# SparkFun_LTE_Stick_LARA_R6.net
KiCad netlist of a schematic drawn in EAGLE
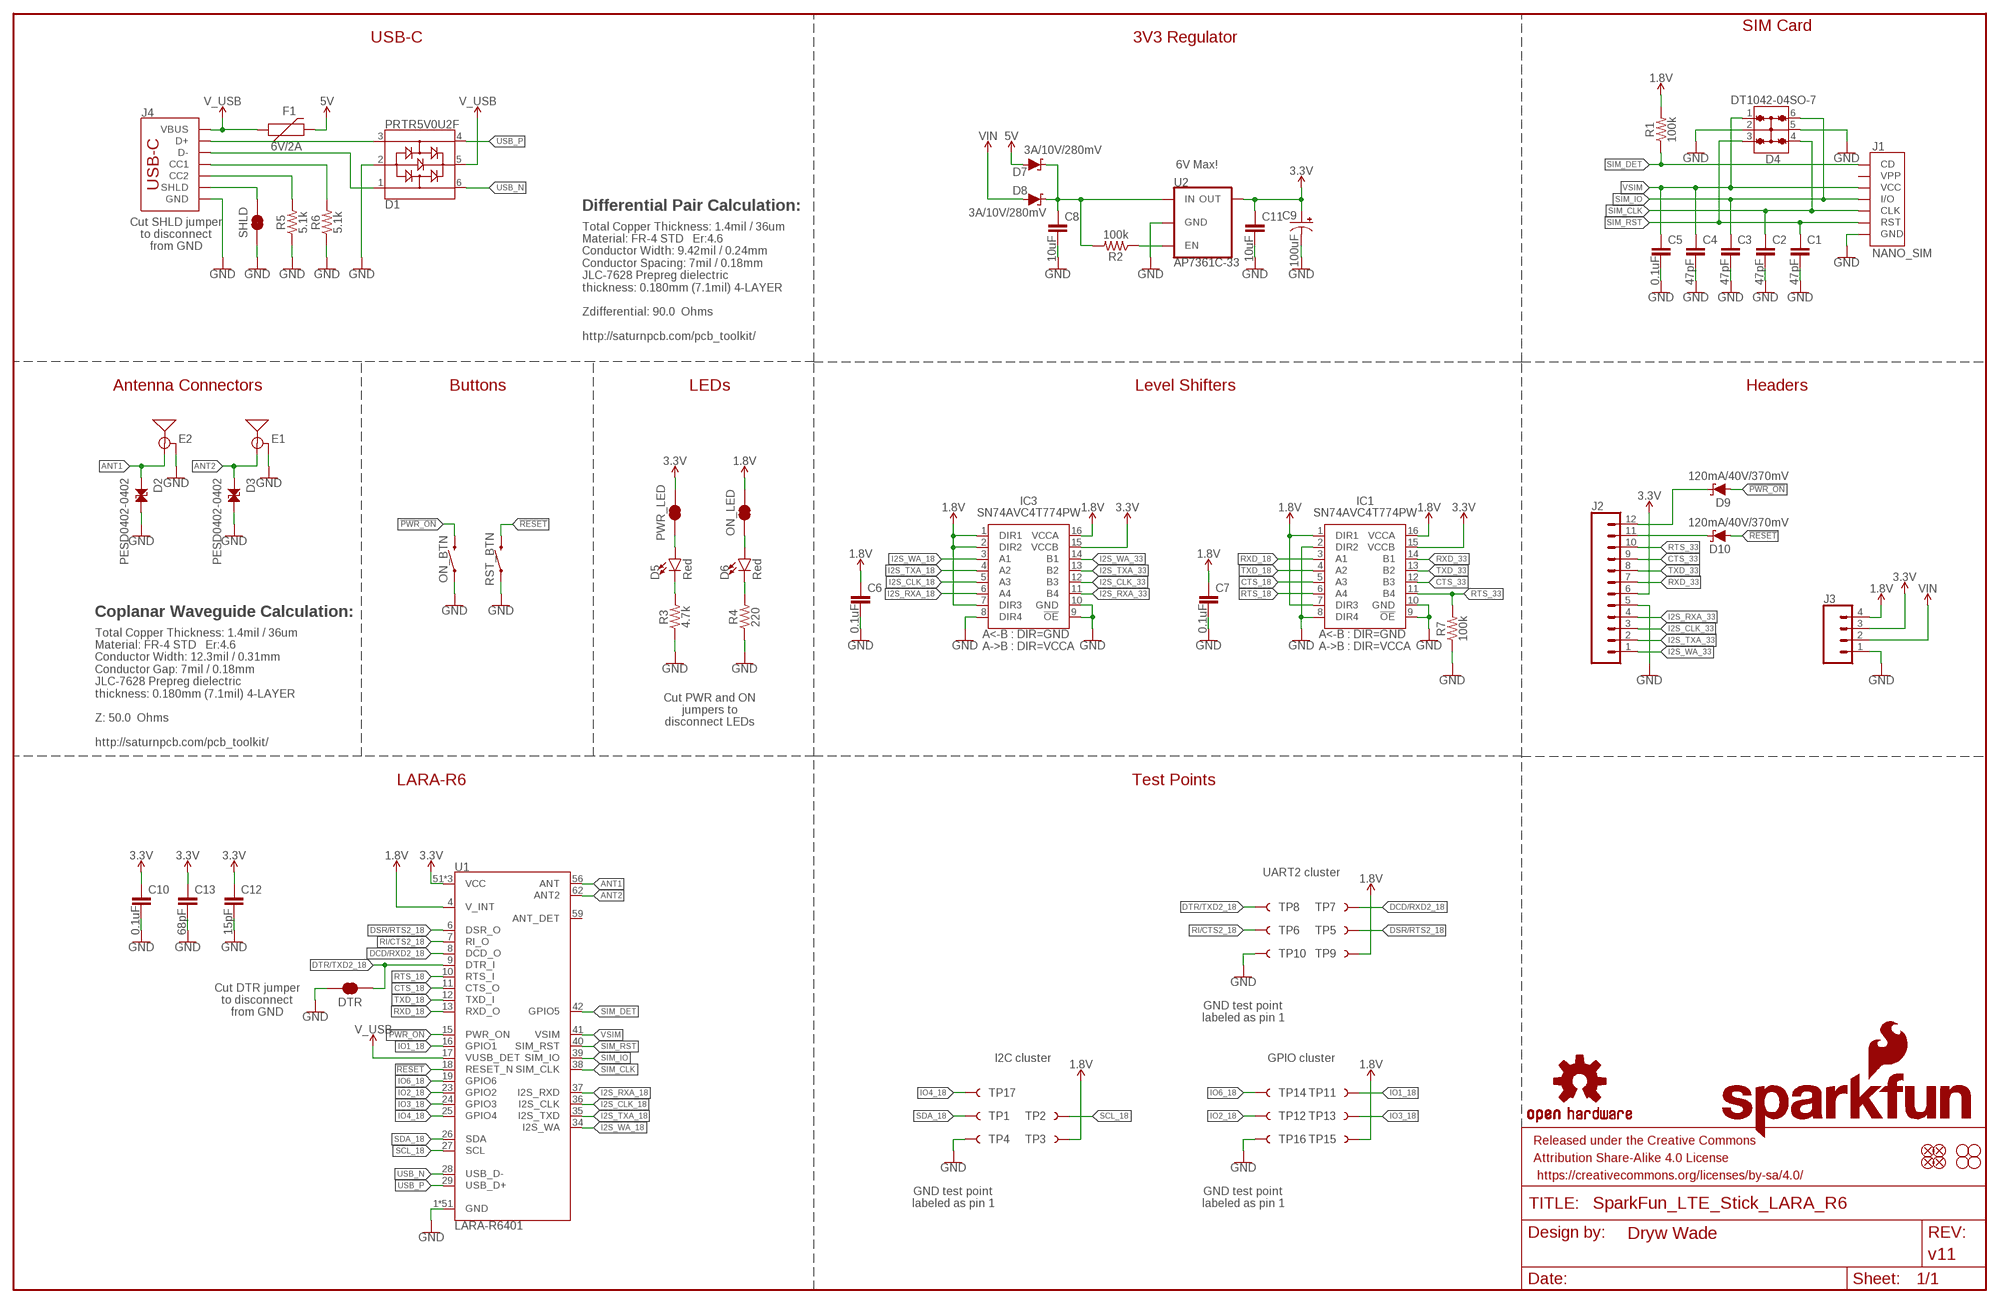
[diagram p0: schematic, sheet 1]

(export (version "E")
  (design (tool "Eeschema 10.0.6"))
  (components
    (comp (ref "C1")
      (value "47pF")
      (footprint "eagle-import:0603")
      (libsource (lib "eagle-import") (part "47PF-0603-50V-5%"))
    )
    (comp (ref "C2")
      (value "47pF")
      (footprint "eagle-import:0603")
      (libsource (lib "eagle-import") (part "47PF-0603-50V-5%"))
    )
    (comp (ref "C3")
      (value "47pF")
      (footprint "eagle-import:0603")
      (libsource (lib "eagle-import") (part "47PF-0603-50V-5%"))
    )
    (comp (ref "C4")
      (value "47pF")
      (footprint "eagle-import:0603")
      (libsource (lib "eagle-import") (part "47PF-0603-50V-5%"))
    )
    (comp (ref "C5")
      (value "0.1uF")
      (footprint "eagle-import:0603")
      (libsource (lib "eagle-import") (part "0.1UF-0603-25V-5%"))
    )
    (comp (ref "C6")
      (value "0.1uF")
      (footprint "eagle-import:0603")
      (libsource (lib "eagle-import") (part "0.1UF-0603-25V-5%"))
    )
    (comp (ref "C7")
      (value "0.1uF")
      (footprint "eagle-import:0603")
      (libsource (lib "eagle-import") (part "0.1UF-0603-25V-5%"))
    )
    (comp (ref "C8")
      (value "10uF")
      (footprint "eagle-import:0805")
      (libsource (lib "eagle-import") (part "10UF-0805-25V-10%"))
    )
    (comp (ref "C9")
      (value "100uF")
      (footprint "eagle-import:PANASONIC_D")
      (libsource (lib "eagle-import") (part "100UF-POLAR-35V-20%(ELEC)"))
    )
    (comp (ref "C10")
      (value "0.1uF")
      (footprint "eagle-import:0603")
      (libsource (lib "eagle-import") (part "0.1UF-0603-25V-5%"))
    )
    (comp (ref "C11")
      (value "10uF")
      (footprint "eagle-import:0805")
      (libsource (lib "eagle-import") (part "10UF-0805-25V-10%"))
    )
    (comp (ref "C12")
      (value "15pF")
      (footprint "eagle-import:0603")
      (libsource (lib "eagle-import") (part "15PF-0603-50V-5%"))
    )
    (comp (ref "C13")
      (value "68pF")
      (footprint "eagle-import:0603")
      (libsource (lib "eagle-import") (part "68PF-0603-50V-5%"))
    )
    (comp (ref "D1")
      (value "PRTR5V0U2F")
      (footprint "eagle-import:SOT886")
      (libsource (lib "eagle-import") (part "PRTR5V0U2F"))
    )
    (comp (ref "D2")
      (value "PESD0402-0402")
      (footprint "eagle-import:0402")
      (fields
        (field (name "DIGIKEY_PART") "PESD0402-140CT-ND")
        (field (name "MOUSE_PART") "650-PESD0402-140")
      )
      (libsource (lib "eagle-import") (part "PESD0402-0402"))
    )
    (comp (ref "D3")
      (value "PESD0402-0402")
      (footprint "eagle-import:0402")
      (fields
        (field (name "DIGIKEY_PART") "PESD0402-140CT-ND")
        (field (name "MOUSE_PART") "650-PESD0402-140")
      )
      (libsource (lib "eagle-import") (part "PESD0402-0402"))
    )
    (comp (ref "D4")
      (value "DT1042-04SO-7")
      (footprint "eagle-import:SOT23-6L")
      (libsource (lib "eagle-import") (part "TVS_DIODE_ARRAY_4_ESDA6V1BC6"))
    )
    (comp (ref "D5")
      (value "Red")
      (footprint "eagle-import:LED-0603")
      (libsource (lib "eagle-import") (part "LED-RED_0603-KB"))
    )
    (comp (ref "D6")
      (value "Red")
      (footprint "eagle-import:LED-0603")
      (libsource (lib "eagle-import") (part "LED-RED_0603-KB"))
    )
    (comp (ref "D7")
      (value "3A/10V/280mV")
      (footprint "eagle-import:SOD-323")
      (libsource (lib "eagle-import") (part "DIODE-SCHOTTKY-BAT60A"))
    )
    (comp (ref "D8")
      (value "3A/10V/280mV")
      (footprint "eagle-import:SOD-323")
      (libsource (lib "eagle-import") (part "DIODE-SCHOTTKY-BAT60A"))
    )
    (comp (ref "D9")
      (value "120mA/40V/370mV")
      (footprint "eagle-import:SOD-523")
      (libsource (lib "eagle-import") (part "DIODE-SCHOTTKY-RB751S40"))
    )
    (comp (ref "D10")
      (value "120mA/40V/370mV")
      (footprint "eagle-import:SOD-523")
      (libsource (lib "eagle-import") (part "DIODE-SCHOTTKY-RB751S40"))
    )
    (comp (ref "DTR")
      (value "JUMPER-SMT_2_NC_TRACE_SILK")
      (footprint "eagle-import:SMT-JUMPER_2_NC_TRACE_SILK")
      (libsource (lib "eagle-import") (part "JUMPER-SMT_2_NC_TRACE_SILK"))
    )
    (comp (ref "E1")
      (value "ANTENNA-SMA-GROUNDEDEDGE_SMA")
      (footprint "eagle-import:SMA-EDGE")
      (fields (field (name "PROD_ID") "CONN-19593"))
      (libsource (lib "eagle-import") (part "ANTENNA-SMA-GROUNDEDEDGE_SMA"))
    )
    (comp (ref "E2")
      (value "ANTENNA-SMA-GROUNDEDEDGE_SMA")
      (footprint "eagle-import:SMA-EDGE")
      (fields (field (name "PROD_ID") "CONN-19593"))
      (libsource (lib "eagle-import") (part "ANTENNA-SMA-GROUNDEDEDGE_SMA"))
    )
    (comp (ref "F1")
      (value "6V/2A")
      (footprint "eagle-import:1210")
      (libsource (lib "eagle-import") (part "PPTC_6V2A"))
    )
    (comp (ref "FD1")
      (value "FIDUCIAL1X2")
      (footprint "eagle-import:FIDUCIAL-1X2")
      (libsource (lib "eagle-import") (part "FIDUCIAL1X2"))
    )
    (comp (ref "FD2")
      (value "FIDUCIAL1X2")
      (footprint "eagle-import:FIDUCIAL-1X2")
      (libsource (lib "eagle-import") (part "FIDUCIAL1X2"))
    )
    (comp (ref "FD3")
      (value "FIDUCIAL1X2")
      (footprint "eagle-import:FIDUCIAL-1X2")
      (libsource (lib "eagle-import") (part "FIDUCIAL1X2"))
    )
    (comp (ref "FD4")
      (value "FIDUCIAL1X2")
      (footprint "eagle-import:FIDUCIAL-1X2")
      (libsource (lib "eagle-import") (part "FIDUCIAL1X2"))
    )
    (comp (ref "FRAME1")
      (value "FRAME-LEDGER")
      (footprint "eagle-import:CREATIVE_COMMONS")
      (fields (field (name "DESIGNER") "Dryw Wade") (field (name "REV") "v11"))
      (libsource (lib "eagle-import") (part "FRAME-LEDGER"))
    )
    (comp (ref "H1")
      (value "STAND-OFF")
      (footprint "eagle-import:STAND-OFF")
      (libsource (lib "eagle-import") (part "STAND-OFF"))
    )
    (comp (ref "H2")
      (value "STAND-OFF")
      (footprint "eagle-import:STAND-OFF")
      (libsource (lib "eagle-import") (part "STAND-OFF"))
    )
    (comp (ref "H3")
      (value "STAND-OFF")
      (footprint "eagle-import:STAND-OFF")
      (libsource (lib "eagle-import") (part "STAND-OFF"))
    )
    (comp (ref "H4")
      (value "STAND-OFF")
      (footprint "eagle-import:STAND-OFF")
      (libsource (lib "eagle-import") (part "STAND-OFF"))
    )
    (comp (ref "IC1")
      (value "SN74AVC4T774PW")
      (footprint "eagle-import:SOP65P640X120-16N")
      (libsource (lib "eagle-import") (part "SN74AVC4T774PW"))
    )
    (comp (ref "IC3")
      (value "SN74AVC4T774PW")
      (footprint "eagle-import:SOP65P640X120-16N")
      (libsource (lib "eagle-import") (part "SN74AVC4T774PW"))
    )
    (comp (ref "J1")
      (value "NANO_SIM")
      (footprint "eagle-import:NANO_SIM_PP")
      (libsource (lib "eagle-import") (part "SIMHOLDER_WITH_CD-PUSHPUSH"))
    )
    (comp (ref "J2")
      (value "CONN_12NO_SILK")
      (footprint "eagle-import:1X12_NO_SILK")
      (libsource (lib "eagle-import") (part "CONN_12NO_SILK"))
    )
    (comp (ref "J3")
      (value "CONN_041X04_NO_SILK_NO_POP")
      (footprint "eagle-import:1X04_NO_SILK")
      (libsource (lib "eagle-import") (part "CONN_041X04_NO_SILK_NO_POP"))
    )
    (comp (ref "J4")
      (value "USB_C_4-LAYER_PADS")
      (footprint "eagle-import:USB-C-16P_4LAYER-PADS")
      (libsource (lib "eagle-import") (part "USB_C_4-LAYER_PADS"))
    )
    (comp (ref "LOGO1")
      (value "SFE_LOGO_NAME_FLAME.1_INCH")
      (footprint "eagle-import:SFE_LOGO_NAME_FLAME_.1")
      (libsource (lib "eagle-import") (part "SFE_LOGO_NAME_FLAME.1_INCH"))
    )
    (comp (ref "LOGO2")
      (value "OSHW-LOGOM")
      (footprint "eagle-import:OSHW-LOGO-M")
      (libsource (lib "eagle-import") (part "OSHW-LOGOM"))
    )
    (comp (ref "ON_BTN")
      (value "MOMENTARY-SWITCH-SPST-SMD-4.6X2.8MM")
      (footprint "eagle-import:TACTILE_SWITCH_SMD_4.6X2.8MM")
      (libsource (lib "eagle-import") (part "MOMENTARY-SWITCH-SPST-SMD-4.6X2.8MM"))
    )
    (comp (ref "ON_LED")
      (value "JUMPER-SMT_2_NC_TRACE_SILK")
      (footprint "eagle-import:SMT-JUMPER_2_NC_TRACE_SILK")
      (libsource (lib "eagle-import") (part "JUMPER-SMT_2_NC_TRACE_SILK"))
    )
    (comp (ref "PWR_LED")
      (value "JUMPER-SMT_2_NC_TRACE_SILK")
      (footprint "eagle-import:SMT-JUMPER_2_NC_TRACE_SILK")
      (libsource (lib "eagle-import") (part "JUMPER-SMT_2_NC_TRACE_SILK"))
    )
    (comp (ref "R1")
      (value "100k")
      (footprint "eagle-import:0603")
      (libsource (lib "eagle-import") (part "100KOHM-0603-1/10W-1%"))
    )
    (comp (ref "R2")
      (value "100k")
      (footprint "eagle-import:0603")
      (libsource (lib "eagle-import") (part "100KOHM-0603-1/10W-1%"))
    )
    (comp (ref "R3")
      (value "4.7k")
      (footprint "eagle-import:0603")
      (libsource (lib "eagle-import") (part "4.7KOHM-0603-1/10W-1%"))
    )
    (comp (ref "R4")
      (value "220")
      (footprint "eagle-import:0603")
      (libsource (lib "eagle-import") (part "220OHM-0603-1/10W-1%"))
    )
    (comp (ref "R5")
      (value "5.1k")
      (footprint "eagle-import:0603")
      (libsource (lib "eagle-import") (part "5.1KOHM5.1KOHM-0603-1/10W-1%"))
    )
    (comp (ref "R6")
      (value "5.1k")
      (footprint "eagle-import:0603")
      (libsource (lib "eagle-import") (part "5.1KOHM5.1KOHM-0603-1/10W-1%"))
    )
    (comp (ref "R7")
      (value "100k")
      (footprint "eagle-import:0603")
      (libsource (lib "eagle-import") (part "100KOHM-0603-1/10W-1%"))
    )
    (comp (ref "RST_BTN")
      (value "MOMENTARY-SWITCH-SPST-SMD-4.6X2.8MM")
      (footprint "eagle-import:TACTILE_SWITCH_SMD_4.6X2.8MM")
      (libsource (lib "eagle-import") (part "MOMENTARY-SWITCH-SPST-SMD-4.6X2.8MM"))
    )
    (comp (ref "SHLD")
      (value "JUMPER-SMT_2_NC_TRACE_SILK")
      (footprint "eagle-import:SMT-JUMPER_2_NC_TRACE_SILK")
      (libsource (lib "eagle-import") (part "JUMPER-SMT_2_NC_TRACE_SILK"))
    )
    (comp (ref "TP1")
      (value "TEST-POINT3X5")
      (footprint "eagle-import:PAD.03X.05")
      (libsource (lib "eagle-import") (part "TEST-POINT3X5"))
    )
    (comp (ref "TP2")
      (value "TEST-POINT3X5")
      (footprint "eagle-import:PAD.03X.05")
      (libsource (lib "eagle-import") (part "TEST-POINT3X5"))
    )
    (comp (ref "TP3")
      (value "TEST-POINT3X5")
      (footprint "eagle-import:PAD.03X.05")
      (libsource (lib "eagle-import") (part "TEST-POINT3X5"))
    )
    (comp (ref "TP4")
      (value "TEST-POINT3X5")
      (footprint "eagle-import:PAD.03X.05")
      (libsource (lib "eagle-import") (part "TEST-POINT3X5"))
    )
    (comp (ref "TP5")
      (value "TEST-POINT3X5")
      (footprint "eagle-import:PAD.03X.05")
      (libsource (lib "eagle-import") (part "TEST-POINT3X5"))
    )
    (comp (ref "TP6")
      (value "TEST-POINT3X5")
      (footprint "eagle-import:PAD.03X.05")
      (libsource (lib "eagle-import") (part "TEST-POINT3X5"))
    )
    (comp (ref "TP7")
      (value "TEST-POINT3X5")
      (footprint "eagle-import:PAD.03X.05")
      (libsource (lib "eagle-import") (part "TEST-POINT3X5"))
    )
    (comp (ref "TP8")
      (value "TEST-POINT3X5")
      (footprint "eagle-import:PAD.03X.05")
      (libsource (lib "eagle-import") (part "TEST-POINT3X5"))
    )
    (comp (ref "TP9")
      (value "TEST-POINT3X5")
      (footprint "eagle-import:PAD.03X.05")
      (libsource (lib "eagle-import") (part "TEST-POINT3X5"))
    )
    (comp (ref "TP10")
      (value "TEST-POINT3X5")
      (footprint "eagle-import:PAD.03X.05")
      (libsource (lib "eagle-import") (part "TEST-POINT3X5"))
    )
    (comp (ref "TP11")
      (value "TEST-POINT3X5")
      (footprint "eagle-import:PAD.03X.05")
      (libsource (lib "eagle-import") (part "TEST-POINT3X5"))
    )
    (comp (ref "TP12")
      (value "TEST-POINT3X5")
      (footprint "eagle-import:PAD.03X.05")
      (libsource (lib "eagle-import") (part "TEST-POINT3X5"))
    )
    (comp (ref "TP13")
      (value "TEST-POINT3X5")
      (footprint "eagle-import:PAD.03X.05")
      (libsource (lib "eagle-import") (part "TEST-POINT3X5"))
    )
    (comp (ref "TP14")
      (value "TEST-POINT3X5")
      (footprint "eagle-import:PAD.03X.05")
      (libsource (lib "eagle-import") (part "TEST-POINT3X5"))
    )
    (comp (ref "TP15")
      (value "TEST-POINT3X5")
      (footprint "eagle-import:PAD.03X.05")
      (libsource (lib "eagle-import") (part "TEST-POINT3X5"))
    )
    (comp (ref "TP16")
      (value "TEST-POINT3X5")
      (footprint "eagle-import:PAD.03X.05")
      (libsource (lib "eagle-import") (part "TEST-POINT3X5"))
    )
    (comp (ref "TP17")
      (value "TEST-POINT3X5")
      (footprint "eagle-import:PAD.03X.05")
      (libsource (lib "eagle-import") (part "TEST-POINT3X5"))
    )
    (comp (ref "U1")
      (value "LARA-R6401")
      (footprint "eagle-import:LARA-LGA")
      (libsource (lib "eagle-import") (part "LARA-R6_R6401_USA"))
    )
    (comp (ref "U2")
      (value "AP7361C-33")
      (footprint "eagle-import:UDFN-8")
      (libsource (lib "eagle-import") (part "AP7361C-33FGEUDFN-8"))
    )
  )
  (nets
    (net (code "1") (name "/~{PWR_ON}") (class "Default")
      (node (ref "D9") (pin "A") (pinfunction "A_A") (pintype "passive"))
      (node (ref "ON_BTN") (pin "3") (pinfunction "2_3") (pintype "passive"))
      (node (ref "ON_BTN") (pin "4") (pinfunction "2_4") (pintype "passive"))
      (node (ref "U1") (pin "15") (pinfunction "PWR_ON_15") (pintype "input"))
    )
    (net (code "2") (name "/~{RESET}") (class "Default")
      (node (ref "D10") (pin "A") (pinfunction "A_A") (pintype "passive"))
      (node (ref "RST_BTN") (pin "3") (pinfunction "2_3") (pintype "passive"))
      (node (ref "RST_BTN") (pin "4") (pinfunction "2_4") (pintype "passive"))
      (node (ref "U1") (pin "18") (pinfunction "RESET_N_18") (pintype "input"))
    )
    (net (code "3") (name "1.8V") (class "Default")
      (node (ref "C6") (pin "1") (pinfunction "1_1") (pintype "passive"))
      (node (ref "C7") (pin "1") (pinfunction "1_1") (pintype "passive"))
      (node (ref "IC1") (pin "1") (pinfunction "DIR1_1") (pintype "input"))
      (node (ref "IC1") (pin "16") (pinfunction "VCCA_16") (pintype "power_in"))
      (node (ref "IC1") (pin "7") (pinfunction "DIR3_7") (pintype "input"))
      (node (ref "IC3") (pin "1") (pinfunction "DIR1_1") (pintype "input"))
      (node (ref "IC3") (pin "16") (pinfunction "VCCA_16") (pintype "power_in"))
      (node (ref "IC3") (pin "2") (pinfunction "DIR2_2") (pintype "input"))
      (node (ref "IC3") (pin "7") (pinfunction "DIR3_7") (pintype "input"))
      (node (ref "J3") (pin "4") (pinfunction "4_4") (pintype "passive"))
      (node (ref "ON_LED") (pin "2") (pinfunction "2_2") (pintype "passive"))
      (node (ref "R1") (pin "2") (pinfunction "2_2") (pintype "passive"))
      (node (ref "TP15") (pin "1") (pinfunction "1_1") (pintype "bidirectional"))
      (node (ref "TP3") (pin "1") (pinfunction "1_1") (pintype "bidirectional"))
      (node (ref "TP9") (pin "1") (pinfunction "1_1") (pintype "bidirectional"))
      (node (ref "U1") (pin "4") (pinfunction "V_INT_4") (pintype "output"))
    )
    (net (code "4") (name "3.3V") (class "Default")
      (node (ref "C10") (pin "1") (pinfunction "1_1") (pintype "passive"))
      (node (ref "C11") (pin "1") (pinfunction "1_1") (pintype "passive"))
      (node (ref "C12") (pin "1") (pinfunction "1_1") (pintype "passive"))
      (node (ref "C13") (pin "1") (pinfunction "1_1") (pintype "passive"))
      (node (ref "C9") (pin "+") (pinfunction "+_+") (pintype "passive"))
      (node (ref "IC1") (pin "15") (pinfunction "VCCB_15") (pintype "power_in"))
      (node (ref "IC3") (pin "15") (pinfunction "VCCB_15") (pintype "power_in"))
      (node (ref "J2") (pin "6") (pinfunction "6_6") (pintype "passive"))
      (node (ref "J3") (pin "3") (pinfunction "3_3") (pintype "passive"))
      (node (ref "PWR_LED") (pin "2") (pinfunction "2_2") (pintype "passive"))
      (node (ref "U1") (pin "51") (pinfunction "VCC_51") (pintype "power_in"))
      (node (ref "U1") (pin "52") (pinfunction "VCC_52") (pintype "power_in"))
      (node (ref "U1") (pin "53") (pinfunction "VCC_53") (pintype "power_in"))
      (node (ref "U2") (pin "1") (pinfunction "OUT_1") (pintype "output"))
    )
    (net (code "5") (name "5V") (class "Default")
      (node (ref "D7") (pin "A") (pinfunction "A_A") (pintype "passive"))
      (node (ref "F1") (pin "2") (pinfunction "2_2") (pintype "bidirectional"))
    )
    (net (code "6") (name "ANT1") (class "Default")
      (node (ref "D2") (pin "1") (pinfunction "1_1") (pintype "bidirectional"))
      (node (ref "E2") (pin "SIG") (pinfunction "SIGNAL_SIG") (pintype "bidirectional"))
      (node (ref "U1") (pin "56") (pinfunction "ANT_56") (pintype "bidirectional"))
    )
    (net (code "7") (name "ANT2") (class "Default")
      (node (ref "D3") (pin "1") (pinfunction "1_1") (pintype "bidirectional"))
      (node (ref "E1") (pin "SIG") (pinfunction "SIGNAL_SIG") (pintype "bidirectional"))
      (node (ref "U1") (pin "62") (pinfunction "ANT2_62") (pintype "bidirectional"))
    )
    (net (code "8") (name "CTS_18") (class "Default")
      (node (ref "IC1") (pin "5") (pinfunction "A3_5") (pintype "bidirectional"))
      (node (ref "U1") (pin "11") (pinfunction "CTS_O_11") (pintype "output"))
    )
    (net (code "9") (name "CTS_33") (class "Default")
      (node (ref "IC1") (pin "12") (pinfunction "B3_12") (pintype "bidirectional"))
      (node (ref "J2") (pin "9") (pinfunction "9_9") (pintype "passive"))
    )
    (net (code "10") (name "DCD{slash}RXD2_18") (class "Default")
      (node (ref "TP7") (pin "1") (pinfunction "1_1") (pintype "bidirectional"))
      (node (ref "U1") (pin "8") (pinfunction "DCD_O_8") (pintype "output"))
    )
    (net (code "11") (name "DSR{slash}RTS2_18") (class "Default")
      (node (ref "TP5") (pin "1") (pinfunction "1_1") (pintype "bidirectional"))
      (node (ref "U1") (pin "6") (pinfunction "DSR_O_6") (pintype "output"))
    )
    (net (code "12") (name "DTR{slash}TXD2_18") (class "Default")
      (node (ref "DTR") (pin "2") (pinfunction "2_2") (pintype "passive"))
      (node (ref "TP8") (pin "1") (pinfunction "1_1") (pintype "bidirectional"))
      (node (ref "U1") (pin "9") (pinfunction "DTR_I_9") (pintype "input"))
    )
    (net (code "13") (name "GND") (class "Default")
      (node (ref "C1") (pin "2") (pinfunction "2_2") (pintype "passive"))
      (node (ref "C10") (pin "2") (pinfunction "2_2") (pintype "passive"))
      (node (ref "C11") (pin "2") (pinfunction "2_2") (pintype "passive"))
      (node (ref "C12") (pin "2") (pinfunction "2_2") (pintype "passive"))
      (node (ref "C13") (pin "2") (pinfunction "2_2") (pintype "passive"))
      (node (ref "C2") (pin "2") (pinfunction "2_2") (pintype "passive"))
      (node (ref "C3") (pin "2") (pinfunction "2_2") (pintype "passive"))
      (node (ref "C4") (pin "2") (pinfunction "2_2") (pintype "passive"))
      (node (ref "C5") (pin "2") (pinfunction "2_2") (pintype "passive"))
      (node (ref "C6") (pin "2") (pinfunction "2_2") (pintype "passive"))
      (node (ref "C7") (pin "2") (pinfunction "2_2") (pintype "passive"))
      (node (ref "C8") (pin "2") (pinfunction "2_2") (pintype "passive"))
      (node (ref "C9") (pin "-") (pinfunction "-_-") (pintype "passive"))
      (node (ref "D1") (pin "2") (pinfunction "2_2") (pintype "power_in"))
      (node (ref "D2") (pin "2") (pinfunction "2_2") (pintype "bidirectional"))
      (node (ref "D3") (pin "2") (pinfunction "2_2") (pintype "bidirectional"))
      (node (ref "D4") (pin "2") (pinfunction "2_2") (pintype "bidirectional"))
      (node (ref "D4") (pin "5") (pinfunction "5_5") (pintype "bidirectional"))
      (node (ref "DTR") (pin "1") (pinfunction "1_1") (pintype "passive"))
      (node (ref "E1") (pin "GND@0") (pinfunction "GND_GND@0") (pintype "bidirectional"))
      (node (ref "E1") (pin "GND@1") (pinfunction "GND_GND@1") (pintype "bidirectional"))
      (node (ref "E1") (pin "GND@2") (pinfunction "GND_GND@2") (pintype "bidirectional"))
      (node (ref "E1") (pin "GND@3") (pinfunction "GND_GND@3") (pintype "bidirectional"))
      (node (ref "E2") (pin "GND@0") (pinfunction "GND_GND@0") (pintype "bidirectional"))
      (node (ref "E2") (pin "GND@1") (pinfunction "GND_GND@1") (pintype "bidirectional"))
      (node (ref "E2") (pin "GND@2") (pinfunction "GND_GND@2") (pintype "bidirectional"))
      (node (ref "E2") (pin "GND@3") (pinfunction "GND_GND@3") (pintype "bidirectional"))
      (node (ref "IC1") (pin "10") (pinfunction "GND_10") (pintype "power_in"))
      (node (ref "IC1") (pin "2") (pinfunction "DIR2_2") (pintype "input"))
      (node (ref "IC1") (pin "8") (pinfunction "DIR4_8") (pintype "input"))
      (node (ref "IC1") (pin "9") (pinfunction "~{OE}_9") (pintype "input"))
      (node (ref "IC3") (pin "10") (pinfunction "GND_10") (pintype "power_in"))
      (node (ref "IC3") (pin "8") (pinfunction "DIR4_8") (pintype "input"))
      (node (ref "IC3") (pin "9") (pinfunction "~{OE}_9") (pintype "input"))
      (node (ref "J1") (pin "A1") (pinfunction "GND_A1") (pintype "power_in"))
      (node (ref "J1") (pin "A2") (pinfunction "GND_A2") (pintype "power_in"))
      (node (ref "J1") (pin "A3") (pinfunction "GND_A3") (pintype "power_in"))
      (node (ref "J1") (pin "A4") (pinfunction "GND_A4") (pintype "power_in"))
      (node (ref "J1") (pin "C5") (pinfunction "GND_C5") (pintype "power_in"))
      (node (ref "J2") (pin "5") (pinfunction "5_5") (pintype "passive"))
      (node (ref "J3") (pin "1") (pinfunction "1_1") (pintype "passive"))
      (node (ref "J4") (pin "GND") (pinfunction "GND_GND") (pintype "bidirectional"))
      (node (ref "J4") (pin "GND2") (pinfunction "GND_GND2") (pintype "bidirectional"))
      (node (ref "ON_BTN") (pin "1") (pinfunction "1_1") (pintype "passive"))
      (node (ref "ON_BTN") (pin "2") (pinfunction "1_2") (pintype "passive"))
      (node (ref "R3") (pin "1") (pinfunction "1_1") (pintype "passive"))
      (node (ref "R4") (pin "1") (pinfunction "1_1") (pintype "passive"))
      (node (ref "R5") (pin "1") (pinfunction "1_1") (pintype "passive"))
      (node (ref "R6") (pin "1") (pinfunction "1_1") (pintype "passive"))
      (node (ref "R7") (pin "1") (pinfunction "1_1") (pintype "passive"))
      (node (ref "RST_BTN") (pin "1") (pinfunction "1_1") (pintype "passive"))
      (node (ref "RST_BTN") (pin "2") (pinfunction "1_2") (pintype "passive"))
      (node (ref "SHLD") (pin "1") (pinfunction "1_1") (pintype "passive"))
      (node (ref "TP10") (pin "1") (pinfunction "1_1") (pintype "bidirectional"))
      (node (ref "TP16") (pin "1") (pinfunction "1_1") (pintype "bidirectional"))
      (node (ref "TP4") (pin "1") (pinfunction "1_1") (pintype "bidirectional"))
      (node (ref "U1") (pin "1") (pinfunction "GND_1") (pintype "power_in"))
      (node (ref "U1") (pin "14") (pinfunction "GND_14") (pintype "power_in"))
      (node (ref "U1") (pin "20") (pinfunction "GND_20") (pintype "power_in"))
      (node (ref "U1") (pin "21") (pinfunction "GND_21") (pintype "power_in"))
      (node (ref "U1") (pin "22") (pinfunction "GND_22") (pintype "power_in"))
      (node (ref "U1") (pin "3") (pinfunction "GND_3") (pintype "power_in"))
      (node (ref "U1") (pin "30") (pinfunction "GND_30") (pintype "power_in"))
      (node (ref "U1") (pin "32") (pinfunction "GND_32") (pintype "power_in"))
      (node (ref "U1") (pin "43") (pinfunction "GND_43") (pintype "power_in"))
      (node (ref "U1") (pin "5") (pinfunction "GND_5") (pintype "power_in"))
      (node (ref "U1") (pin "50") (pinfunction "GND_50") (pintype "power_in"))
      (node (ref "U1") (pin "54") (pinfunction "GND_54") (pintype "power_in"))
      (node (ref "U1") (pin "55") (pinfunction "GND_55") (pintype "power_in"))
      (node (ref "U1") (pin "57") (pinfunction "GND_57") (pintype "power_in"))
      (node (ref "U1") (pin "58") (pinfunction "GND_58") (pintype "power_in"))
      (node (ref "U1") (pin "60") (pinfunction "GND_60") (pintype "power_in"))
      (node (ref "U1") (pin "61") (pinfunction "GND_61") (pintype "power_in"))
      (node (ref "U1") (pin "63") (pinfunction "GND_63") (pintype "power_in"))
      (node (ref "U1") (pin "64") (pinfunction "GND_64") (pintype "power_in"))
      (node (ref "U1") (pin "65") (pinfunction "GND_65") (pintype "power_in"))
      (node (ref "U1") (pin "66") (pinfunction "GND_66") (pintype "power_in"))
      (node (ref "U1") (pin "67") (pinfunction "GND_67") (pintype "power_in"))
      (node (ref "U1") (pin "68") (pinfunction "GND_68") (pintype "power_in"))
      (node (ref "U1") (pin "69") (pinfunction "GND_69") (pintype "power_in"))
      (node (ref "U1") (pin "70") (pinfunction "GND_70") (pintype "power_in"))
      (node (ref "U1") (pin "71") (pinfunction "GND_71") (pintype "power_in"))
      (node (ref "U1") (pin "72") (pinfunction "GND_72") (pintype "power_in"))
      (node (ref "U1") (pin "73") (pinfunction "GND_73") (pintype "power_in"))
      (node (ref "U1") (pin "74") (pinfunction "GND_74") (pintype "power_in"))
      (node (ref "U1") (pin "75") (pinfunction "GND_75") (pintype "power_in"))
      (node (ref "U1") (pin "76") (pinfunction "GND_76") (pintype "power_in"))
      (node (ref "U1") (pin "77") (pinfunction "GND_77") (pintype "power_in"))
      (node (ref "U1") (pin "78") (pinfunction "GND_78") (pintype "power_in"))
      (node (ref "U1") (pin "79") (pinfunction "GND_79") (pintype "power_in"))
      (node (ref "U1") (pin "80") (pinfunction "GND_80") (pintype "power_in"))
      (node (ref "U1") (pin "81") (pinfunction "GND_81") (pintype "power_in"))
      (node (ref "U1") (pin "82") (pinfunction "GND_82") (pintype "power_in"))
      (node (ref "U1") (pin "83") (pinfunction "GND_83") (pintype "power_in"))
      (node (ref "U1") (pin "84") (pinfunction "GND_84") (pintype "power_in"))
      (node (ref "U1") (pin "85") (pinfunction "GND_85") (pintype "power_in"))
      (node (ref "U1") (pin "86") (pinfunction "GND_86") (pintype "power_in"))
      (node (ref "U1") (pin "87") (pinfunction "GND_87") (pintype "power_in"))
      (node (ref "U1") (pin "88") (pinfunction "GND_88") (pintype "power_in"))
      (node (ref "U1") (pin "89") (pinfunction "GND_89") (pintype "power_in"))
      (node (ref "U1") (pin "90") (pinfunction "GND_90") (pintype "power_in"))
      (node (ref "U1") (pin "91") (pinfunction "GND_91") (pintype "power_in"))
      (node (ref "U1") (pin "92") (pinfunction "GND_92") (pintype "power_in"))
      (node (ref "U1") (pin "93") (pinfunction "GND_93") (pintype "power_in"))
      (node (ref "U1") (pin "94") (pinfunction "GND_94") (pintype "power_in"))
      (node (ref "U1") (pin "95") (pinfunction "GND_95") (pintype "power_in"))
      (node (ref "U1") (pin "96") (pinfunction "GND_96") (pintype "power_in"))
      (node (ref "U2") (pin "4") (pinfunction "GND_4") (pintype "input"))
      (node (ref "U2") (pin "EP") (pinfunction "GND_EP") (pintype "input"))
    )
    (net (code "14") (name "I2S_CLK_18") (class "Default")
      (node (ref "IC3") (pin "5") (pinfunction "A3_5") (pintype "bidirectional"))
      (node (ref "U1") (pin "36") (pinfunction "I2S_CLK_36") (pintype "output"))
    )
    (net (code "15") (name "I2S_CLK_33") (class "Default")
      (node (ref "IC3") (pin "12") (pinfunction "B3_12") (pintype "bidirectional"))
      (node (ref "J2") (pin "3") (pinfunction "3_3") (pintype "passive"))
    )
    (net (code "16") (name "I2S_RXA_18") (class "Default")
      (node (ref "IC3") (pin "6") (pinfunction "A4_6") (pintype "bidirectional"))
      (node (ref "U1") (pin "37") (pinfunction "I2S_RXD_37") (pintype "input"))
    )
    (net (code "17") (name "I2S_RXA_33") (class "Default")
      (node (ref "IC3") (pin "11") (pinfunction "B4_11") (pintype "bidirectional"))
      (node (ref "J2") (pin "4") (pinfunction "4_4") (pintype "passive"))
    )
    (net (code "18") (name "I2S_TXA_18") (class "Default")
      (node (ref "IC3") (pin "4") (pinfunction "A2_4") (pintype "bidirectional"))
      (node (ref "U1") (pin "35") (pinfunction "I2S_TXD_35") (pintype "output"))
    )
    (net (code "19") (name "I2S_TXA_33") (class "Default")
      (node (ref "IC3") (pin "13") (pinfunction "B2_13") (pintype "bidirectional"))
      (node (ref "J2") (pin "2") (pinfunction "2_2") (pintype "passive"))
    )
    (net (code "20") (name "I2S_WA_18") (class "Default")
      (node (ref "IC3") (pin "3") (pinfunction "A1_3") (pintype "bidirectional"))
      (node (ref "U1") (pin "34") (pinfunction "I2S_WA_34") (pintype "output"))
    )
    (net (code "21") (name "I2S_WA_33") (class "Default")
      (node (ref "IC3") (pin "14") (pinfunction "B1_14") (pintype "bidirectional"))
      (node (ref "J2") (pin "1") (pinfunction "1_1") (pintype "passive"))
    )
    (net (code "22") (name "IO1_18") (class "Default")
      (node (ref "TP11") (pin "1") (pinfunction "1_1") (pintype "bidirectional"))
      (node (ref "U1") (pin "16") (pinfunction "GPIO1_16") (pintype "bidirectional"))
    )
    (net (code "23") (name "IO2_18") (class "Default")
      (node (ref "TP12") (pin "1") (pinfunction "1_1") (pintype "bidirectional"))
      (node (ref "U1") (pin "23") (pinfunction "GPIO2_23") (pintype "bidirectional"))
    )
    (net (code "24") (name "IO3_18") (class "Default")
      (node (ref "TP13") (pin "1") (pinfunction "1_1") (pintype "bidirectional"))
      (node (ref "U1") (pin "24") (pinfunction "GPIO3_24") (pintype "bidirectional"))
    )
    (net (code "25") (name "IO4_18") (class "Default")
      (node (ref "TP17") (pin "1") (pinfunction "1_1") (pintype "bidirectional"))
      (node (ref "U1") (pin "25") (pinfunction "GPIO4_25") (pintype "bidirectional"))
    )
    (net (code "26") (name "IO6_18") (class "Default")
      (node (ref "TP14") (pin "1") (pinfunction "1_1") (pintype "bidirectional"))
      (node (ref "U1") (pin "19") (pinfunction "GPIO6_19") (pintype "bidirectional"))
    )
    (net (code "27") (name "Net-(D1-Pad1)") (class "Default")
      (node (ref "D1") (pin "1") (pinfunction "1_1") (pintype "bidirectional"))
      (node (ref "J4") (pin "A7") (pinfunction "D-_A7") (pintype "bidirectional"))
      (node (ref "J4") (pin "B7") (pinfunction "D-_B7") (pintype "bidirectional"))
    )
    (net (code "28") (name "Net-(D1-Pad3)") (class "Default")
      (node (ref "D1") (pin "3") (pinfunction "3_3") (pintype "bidirectional"))
      (node (ref "J4") (pin "A6") (pinfunction "D+_A6") (pintype "bidirectional"))
      (node (ref "J4") (pin "B6") (pinfunction "D+_B6") (pintype "bidirectional"))
    )
    (net (code "29") (name "Net-(D5-PadA)") (class "Default")
      (node (ref "D5") (pin "A") (pinfunction "A_A") (pintype "passive"))
      (node (ref "PWR_LED") (pin "1") (pinfunction "1_1") (pintype "passive"))
    )
    (net (code "30") (name "Net-(D5-PadC)") (class "Default")
      (node (ref "D5") (pin "C") (pinfunction "C_C") (pintype "passive"))
      (node (ref "R3") (pin "2") (pinfunction "2_2") (pintype "passive"))
    )
    (net (code "31") (name "Net-(D6-PadA)") (class "Default")
      (node (ref "D6") (pin "A") (pinfunction "A_A") (pintype "passive"))
      (node (ref "ON_LED") (pin "1") (pinfunction "1_1") (pintype "passive"))
    )
    (net (code "32") (name "Net-(D6-PadC)") (class "Default")
      (node (ref "D6") (pin "C") (pinfunction "C_C") (pintype "passive"))
      (node (ref "R4") (pin "2") (pinfunction "2_2") (pintype "passive"))
    )
    (net (code "33") (name "Net-(D9-PadC)") (class "Default")
      (node (ref "D9") (pin "C") (pinfunction "C_C") (pintype "passive"))
      (node (ref "J2") (pin "12") (pinfunction "12_12") (pintype "passive"))
    )
    (net (code "34") (name "Net-(D10-PadC)") (class "Default")
      (node (ref "D10") (pin "C") (pinfunction "C_C") (pintype "passive"))
      (node (ref "J2") (pin "11") (pinfunction "11_11") (pintype "passive"))
    )
    (net (code "35") (name "Net-(J4-CC1)") (class "Default")
      (node (ref "J4") (pin "A5") (pinfunction "CC1_A5") (pintype "bidirectional"))
      (node (ref "R6") (pin "2") (pinfunction "2_2") (pintype "passive"))
    )
    (net (code "36") (name "Net-(J4-CC2)") (class "Default")
      (node (ref "J4") (pin "B5") (pinfunction "CC2_B5") (pintype "bidirectional"))
      (node (ref "R5") (pin "2") (pinfunction "2_2") (pintype "passive"))
    )
    (net (code "37") (name "Net-(J4-SHLD-PadSHLD1)") (class "Default")
      (node (ref "J4") (pin "SHLD1") (pinfunction "SHLD_SHLD1") (pintype "bidirectional"))
      (node (ref "J4") (pin "SHLD2") (pinfunction "SHLD_SHLD2") (pintype "bidirectional"))
      (node (ref "J4") (pin "SHLD3") (pinfunction "SHLD_SHLD3") (pintype "bidirectional"))
      (node (ref "J4") (pin "SHLD4") (pinfunction "SHLD_SHLD4") (pintype "bidirectional"))
      (node (ref "SHLD") (pin "2") (pinfunction "2_2") (pintype "passive"))
    )
    (net (code "38") (name "Net-(U2-EN)") (class "Default")
      (node (ref "R2") (pin "1") (pinfunction "1_1") (pintype "passive"))
      (node (ref "U2") (pin "5") (pinfunction "EN_5") (pintype "bidirectional"))
    )
    (net (code "39") (name "Net-(U2-IN)") (class "Default")
      (node (ref "C8") (pin "1") (pinfunction "1_1") (pintype "passive"))
      (node (ref "D7") (pin "C") (pinfunction "C_C") (pintype "passive"))
      (node (ref "D8") (pin "C") (pinfunction "C_C") (pintype "passive"))
      (node (ref "R2") (pin "2") (pinfunction "2_2") (pintype "passive"))
      (node (ref "U2") (pin "8") (pinfunction "IN_8") (pintype "input"))
    )
    (net (code "40") (name "RI{slash}CTS2_18") (class "Default")
      (node (ref "TP6") (pin "1") (pinfunction "1_1") (pintype "bidirectional"))
      (node (ref "U1") (pin "7") (pinfunction "RI_O_7") (pintype "output"))
    )
    (net (code "41") (name "RTS_18") (class "Default")
      (node (ref "IC1") (pin "6") (pinfunction "A4_6") (pintype "bidirectional"))
      (node (ref "U1") (pin "10") (pinfunction "RTS_I_10") (pintype "input"))
    )
    (net (code "42") (name "RTS_33") (class "Default")
      (node (ref "IC1") (pin "11") (pinfunction "B4_11") (pintype "bidirectional"))
      (node (ref "J2") (pin "10") (pinfunction "10_10") (pintype "passive"))
      (node (ref "R7") (pin "2") (pinfunction "2_2") (pintype "passive"))
    )
    (net (code "43") (name "RXD_18") (class "Default")
      (node (ref "IC1") (pin "3") (pinfunction "A1_3") (pintype "bidirectional"))
      (node (ref "U1") (pin "13") (pinfunction "RXD_O_13") (pintype "output"))
    )
    (net (code "44") (name "RXD_33") (class "Default")
      (node (ref "IC1") (pin "14") (pinfunction "B1_14") (pintype "bidirectional"))
      (node (ref "J2") (pin "7") (pinfunction "7_7") (pintype "passive"))
    )
    (net (code "45") (name "SCL_18") (class "Default")
      (node (ref "TP2") (pin "1") (pinfunction "1_1") (pintype "bidirectional"))
      (node (ref "U1") (pin "27") (pinfunction "SCL_27") (pintype "bidirectional"))
    )
    (net (code "46") (name "SDA_18") (class "Default")
      (node (ref "TP1") (pin "1") (pinfunction "1_1") (pintype "bidirectional"))
      (node (ref "U1") (pin "26") (pinfunction "SDA_26") (pintype "bidirectional"))
    )
    (net (code "47") (name "SIM_CLK") (class "Default")
      (node (ref "C2") (pin "1") (pinfunction "1_1") (pintype "passive"))
      (node (ref "D4") (pin "4") (pinfunction "4_4") (pintype "bidirectional"))
      (node (ref "J1") (pin "C3") (pinfunction "CLK_C3") (pintype "input"))
      (node (ref "U1") (pin "38") (pinfunction "SIM_CLK_38") (pintype "output"))
    )
    (net (code "48") (name "SIM_DET") (class "Default")
      (node (ref "J1") (pin "CD") (pinfunction "CD_CD") (pintype "input"))
      (node (ref "R1") (pin "1") (pinfunction "1_1") (pintype "passive"))
      (node (ref "U1") (pin "42") (pinfunction "GPIO5_42") (pintype "bidirectional"))
    )
    (net (code "49") (name "SIM_IO") (class "Default")
      (node (ref "C3") (pin "1") (pinfunction "1_1") (pintype "passive"))
      (node (ref "D4") (pin "6") (pinfunction "6_6") (pintype "bidirectional"))
      (node (ref "J1") (pin "C7") (pinfunction "I/O_C7") (pintype "bidirectional"))
      (node (ref "U1") (pin "39") (pinfunction "SIM_IO_39") (pintype "bidirectional"))
    )
    (net (code "50") (name "SIM_RST") (class "Default")
      (node (ref "C1") (pin "1") (pinfunction "1_1") (pintype "passive"))
      (node (ref "D4") (pin "3") (pinfunction "3_3") (pintype "bidirectional"))
      (node (ref "J1") (pin "C2") (pinfunction "RST_C2") (pintype "input"))
      (node (ref "U1") (pin "40") (pinfunction "SIM_RST_40") (pintype "output"))
    )
    (net (code "51") (name "TXD_18") (class "Default")
      (node (ref "IC1") (pin "4") (pinfunction "A2_4") (pintype "bidirectional"))
      (node (ref "U1") (pin "12") (pinfunction "TXD_I_12") (pintype "input"))
    )
    (net (code "52") (name "TXD_33") (class "Default")
      (node (ref "IC1") (pin "13") (pinfunction "B2_13") (pintype "bidirectional"))
      (node (ref "J2") (pin "8") (pinfunction "8_8") (pintype "passive"))
    )
    (net (code "53") (name "USB_N") (class "Default")
      (node (ref "D1") (pin "6") (pinfunction "6_6") (pintype "bidirectional"))
      (node (ref "U1") (pin "28") (pinfunction "USB_D-_28") (pintype "bidirectional"))
    )
    (net (code "54") (name "USB_P") (class "Default")
      (node (ref "D1") (pin "4") (pinfunction "4_4") (pintype "bidirectional"))
      (node (ref "U1") (pin "29") (pinfunction "USB_D+_29") (pintype "bidirectional"))
    )
    (net (code "55") (name "VIN") (class "Default")
      (node (ref "D8") (pin "A") (pinfunction "A_A") (pintype "passive"))
      (node (ref "J3") (pin "2") (pinfunction "2_2") (pintype "passive"))
    )
    (net (code "56") (name "VSIM") (class "Default")
      (node (ref "C4") (pin "1") (pinfunction "1_1") (pintype "passive"))
      (node (ref "C5") (pin "1") (pinfunction "1_1") (pintype "passive"))
      (node (ref "D4") (pin "1") (pinfunction "1_1") (pintype "bidirectional"))
      (node (ref "J1") (pin "C1") (pinfunction "VCC_C1") (pintype "power_in"))
      (node (ref "U1") (pin "41") (pinfunction "VSIM_41") (pintype "output"))
    )
    (net (code "57") (name "V_USB") (class "Default")
      (node (ref "D1") (pin "5") (pinfunction "5_5") (pintype "power_in"))
      (node (ref "F1") (pin "1") (pinfunction "1_1") (pintype "bidirectional"))
      (node (ref "J4") (pin "VBUS1") (pinfunction "VBUS_VBUS1") (pintype "bidirectional"))
      (node (ref "J4") (pin "VBUS2") (pinfunction "VBUS_VBUS2") (pintype "bidirectional"))
      (node (ref "U1") (pin "17") (pinfunction "VUSB_DET_17") (pintype "input"))
    )
    (net (code "58") (name "unconnected-(J1-VPP-PadC6)") (class "Default")
      (node (ref "J1") (pin "C6") (pinfunction "VPP_C6") (pintype "input"))
    )
    (net (code "59") (name "unconnected-(U1-ANT_DET-Pad59)") (class "Default")
      (node (ref "U1") (pin "59") (pinfunction "ANT_DET_59") (pintype "input"))
    )
  )
)
